# Sch_Raspi_Hat_V2.net
KiCad netlist of a schematic drawn in Altium Designer
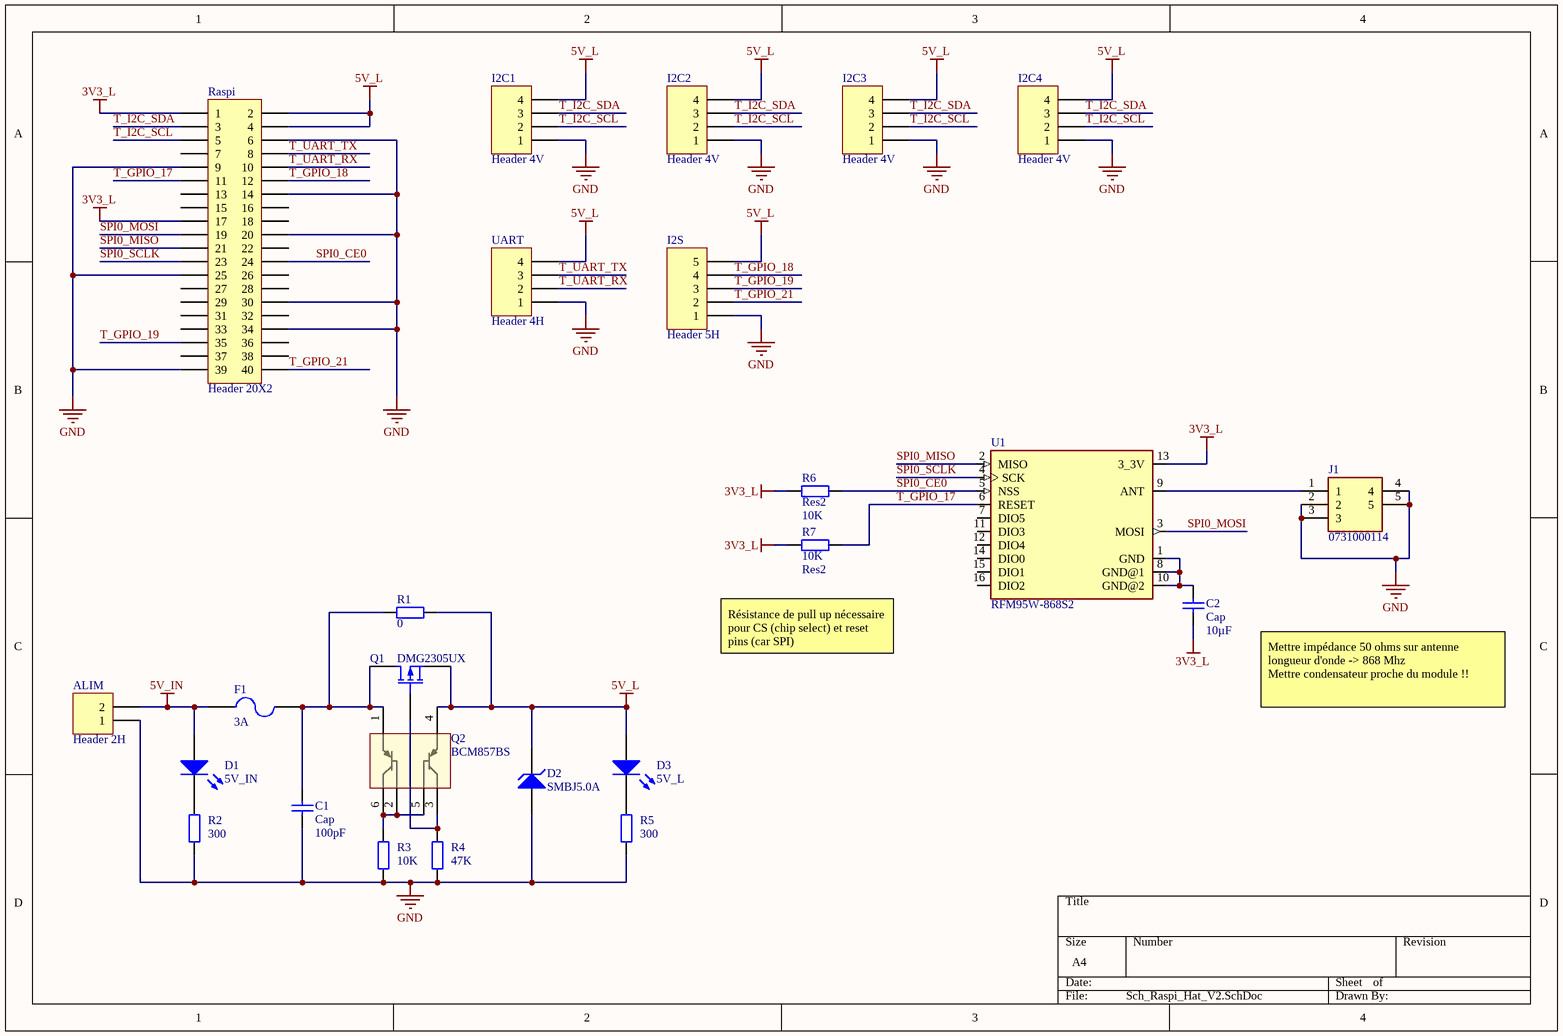
[diagram p0: Sch_Raspi_Hat_V2.SchDoc]

(export (version "E")
  (design (tool "Eeschema 10.0.6"))
  (components
    (comp (ref "ALIM")
      (value "Header 2H")
      (footprint "Molex_MiniFitJr_2x1H")
      (description "Header, 2-Pin, Right Angle")
      (fields (field (name "PUBLISHER") "Altium Limited"))
      (libsource (lib "Miscellaneous Connectors") (part "Header 2H"))
    )
    (comp (ref "C1")
      (value "Cap")
      (footprint "Capacitor 1206")
      (description "Capacitor")
      (fields (field (name "ALTIUM_VALUE") "100pF") (field (name "PUBLISHER") "Altium Limited"))
      (libsource (lib "Miscellaneous Devices") (part "Cap"))
    )
    (comp (ref "C2")
      (value "Cap")
      (footprint "Capacitor 1206")
      (description "Capacitor")
      (fields (field (name "ALTIUM_VALUE") "10µF") (field (name "PUBLISHER") "Altium Limited"))
      (libsource (lib "Miscellaneous Devices") (part "Cap"))
    )
    (comp (ref "D1")
      (value "5V_IN")
      (footprint "KP-3216SEC")
      (description "Typical RED, GREEN, YELLOW, AMBER GaAs LED")
      (fields (field (name "PUBLISHER") "Altium Limited"))
      (libsource (lib "Miscellaneous Devices") (part "LED2"))
    )
    (comp (ref "D2")
      (value "SMBJ5.0A")
      (footprint "SMB")
      (description "Zener Diode")
      (fields (field (name "PUBLISHER") "Altium Limited"))
      (libsource (lib "Miscellaneous Devices") (part "D Zener"))
    )
    (comp (ref "D3")
      (value "5V_L")
      (footprint "KP-3216SEC")
      (description "Typical RED, GREEN, YELLOW, AMBER GaAs LED")
      (fields (field (name "PUBLISHER") "Altium Limited"))
      (libsource (lib "Miscellaneous Devices") (part "LED2"))
    )
    (comp (ref "F1")
      (value "3A")
      (footprint "Resistor 1206")
      (description "Fuse")
      (fields (field (name "PUBLISHER") "Altium Limited"))
      (libsource (lib "Miscellaneous Devices") (part "Fuse 2"))
    )
    (comp (ref "I2C1")
      (value "Header 4V")
      (footprint "B4BXHALFSN")
      (description "Header, 4-Pin, Right Angle")
      (fields (field (name "PUBLISHER") "Altium Limited"))
      (libsource (lib "Miscellaneous Connectors") (part "Header 4H"))
    )
    (comp (ref "I2C2")
      (value "Header 4V")
      (footprint "B4BXHALFSN")
      (description "Header, 4-Pin, Right Angle")
      (fields (field (name "PUBLISHER") "Altium Limited"))
      (libsource (lib "Miscellaneous Connectors") (part "Header 4H"))
    )
    (comp (ref "I2C3")
      (value "Header 4V")
      (footprint "B4BXHALFSN")
      (description "Header, 4-Pin, Right Angle")
      (fields (field (name "PUBLISHER") "Altium Limited"))
      (libsource (lib "Miscellaneous Connectors") (part "Header 4H"))
    )
    (comp (ref "I2C4")
      (value "Header 4V")
      (footprint "B4BXHALFSN")
      (description "Header, 4-Pin, Right Angle")
      (fields (field (name "PUBLISHER") "Altium Limited"))
      (libsource (lib "Miscellaneous Connectors") (part "Header 4H"))
    )
    (comp (ref "I2S")
      (value "Header 5H")
      (footprint "S5B-XH-A")
      (description "Header, 5-Pin, Right Angle")
      (fields (field (name "PUBLISHER") "Altium Limited"))
      (libsource (lib "Miscellaneous Connectors") (part "Header 5H"))
    )
    (comp (ref "J1")
      (value "0731000114")
      (footprint "0731000114")
      (description "Connector")
      (libsource (lib "*") (part "0731000114"))
    )
    (comp (ref "Q1")
      (value "DMG2305UX")
      (footprint "SOT23_L")
      (description "P-Channel MOSFET")
      (fields (field (name "PUBLISHER") "Altium Limited"))
      (libsource (lib "Miscellaneous Devices") (part "MOSFET-P"))
    )
    (comp (ref "Q2")
      (value "BCM857BS")
      (footprint "SOT65P210X110-6N")
      (description "Transistor")
      (libsource (lib "SamacSys") (part "BCM857BS"))
    )
    (comp (ref "R1")
      (value "0")
      (footprint "Resistor 1206")
      (description "Resistor")
      (fields (field (name "Comment") "Res2") (field (name "PUBLISHER") "Altium Limited"))
      (libsource (lib "") (part "Res2_2"))
    )
    (comp (ref "R2")
      (value "300")
      (footprint "Resistor 1206")
      (description "Resistor")
      (fields (field (name "Comment") "Res2") (field (name "PUBLISHER") "Altium Limited"))
      (libsource (lib "Miscellaneous Devices") (part "Res2"))
    )
    (comp (ref "R3")
      (value "10K")
      (footprint "Resistor 1206")
      (description "Resistor")
      (fields (field (name "Comment") "Res2") (field (name "PUBLISHER") "Altium Limited"))
      (libsource (lib "Miscellaneous Devices") (part "Res2"))
    )
    (comp (ref "R4")
      (value "47K")
      (footprint "Resistor 1206")
      (description "Resistor")
      (fields (field (name "Comment") "Res2") (field (name "PUBLISHER") "Altium Limited"))
      (libsource (lib "Miscellaneous Devices") (part "Res2"))
    )
    (comp (ref "R5")
      (value "300")
      (footprint "Resistor 1206")
      (description "Resistor")
      (fields (field (name "Comment") "Res2") (field (name "PUBLISHER") "Altium Limited"))
      (libsource (lib "Miscellaneous Devices") (part "Res2"))
    )
    (comp (ref "R6")
      (value "Res2")
      (footprint "Resistor 1206")
      (description "Resistor")
      (fields (field (name "ALTIUM_VALUE") "10K") (field (name "PUBLISHER") "Altium Limited"))
      (libsource (lib "") (part "Res2_1"))
    )
    (comp (ref "R7")
      (value "Res2")
      (footprint "Resistor 1206")
      (description "Resistor")
      (fields (field (name "ALTIUM_VALUE") "10K") (field (name "PUBLISHER") "Altium Limited"))
      (libsource (lib "") (part "Res2_1"))
    )
    (comp (ref "Raspi")
      (value "Header 20X2")
      (footprint "HDR2X20")
      (description "Header, 20-Pin, Dual row")
      (fields (field (name "PUBLISHER") "Altium Limited"))
      (libsource (lib "Miscellaneous Connectors") (part "Header 20X2"))
    )
    (comp (ref "U1")
      (value "RFM95W-868S2")
      (footprint "XCVR_RFM95W-868S2")
      (description "General ISM < 1GHz LoRaâ„¢ Transceiver Module 868MHz Antenna Not Included Surface Mount")
      (fields (field (name "MF") "RF"))
      (libsource (lib "LORA_RFM95W-868S2") (part "RFM95W-868S2"))
    )
    (comp (ref "UART")
      (value "Header 4H")
      (footprint "S4B-XH-A")
      (description "Header, 4-Pin, Right Angle")
      (fields (field (name "PUBLISHER") "Altium Limited"))
      (libsource (lib "Miscellaneous Connectors") (part "Header 4H"))
    )
  )
  (nets
    (net (code "1") (name "/SPI0_CE0") (class "Default")
      (node (ref "R6") (pin "2") (pinfunction "2_2") (pintype "passive"))
      (node (ref "Raspi") (pin "24") (pinfunction "24_24") (pintype "passive"))
      (node (ref "U1") (pin "5") (pinfunction "NSS_5") (pintype "input"))
    )
    (net (code "2") (name "/SPI0_MISO") (class "Default")
      (node (ref "Raspi") (pin "21") (pinfunction "21_21") (pintype "passive"))
      (node (ref "U1") (pin "2") (pinfunction "MISO_2") (pintype "input"))
    )
    (net (code "3") (name "/SPI0_MOSI") (class "Default")
      (node (ref "Raspi") (pin "19") (pinfunction "19_19") (pintype "passive"))
      (node (ref "U1") (pin "3") (pinfunction "MOSI_3") (pintype "output"))
    )
    (net (code "4") (name "/SPI0_SCLK") (class "Default")
      (node (ref "Raspi") (pin "23") (pinfunction "23_23") (pintype "passive"))
      (node (ref "U1") (pin "4") (pinfunction "SCK_4") (pintype "input"))
    )
    (net (code "5") (name "/T_GPIO_17") (class "Default")
      (node (ref "R7") (pin "2") (pinfunction "2_2") (pintype "passive"))
      (node (ref "Raspi") (pin "11") (pinfunction "11_11") (pintype "passive"))
      (node (ref "U1") (pin "6") (pinfunction "RESET_6") (pintype "bidirectional"))
    )
    (net (code "6") (name "/T_GPIO_18") (class "Default")
      (node (ref "I2S") (pin "4") (pinfunction "4_4") (pintype "passive"))
      (node (ref "Raspi") (pin "12") (pinfunction "12_12") (pintype "passive"))
    )
    (net (code "7") (name "/T_GPIO_19") (class "Default")
      (node (ref "I2S") (pin "3") (pinfunction "3_3") (pintype "passive"))
      (node (ref "Raspi") (pin "35") (pinfunction "35_35") (pintype "passive"))
    )
    (net (code "8") (name "/T_GPIO_21") (class "Default")
      (node (ref "I2S") (pin "2") (pinfunction "2_2") (pintype "passive"))
      (node (ref "Raspi") (pin "40") (pinfunction "40_40") (pintype "passive"))
    )
    (net (code "9") (name "/T_I2C_SCL") (class "Default")
      (node (ref "I2C1") (pin "2") (pinfunction "2_2") (pintype "passive"))
      (node (ref "I2C2") (pin "2") (pinfunction "2_2") (pintype "passive"))
      (node (ref "I2C3") (pin "2") (pinfunction "2_2") (pintype "passive"))
      (node (ref "I2C4") (pin "2") (pinfunction "2_2") (pintype "passive"))
      (node (ref "Raspi") (pin "5") (pinfunction "5_5") (pintype "passive"))
    )
    (net (code "10") (name "/T_I2C_SDA") (class "Default")
      (node (ref "I2C1") (pin "3") (pinfunction "3_3") (pintype "passive"))
      (node (ref "I2C2") (pin "3") (pinfunction "3_3") (pintype "passive"))
      (node (ref "I2C3") (pin "3") (pinfunction "3_3") (pintype "passive"))
      (node (ref "I2C4") (pin "3") (pinfunction "3_3") (pintype "passive"))
      (node (ref "Raspi") (pin "3") (pinfunction "3_3") (pintype "passive"))
    )
    (net (code "11") (name "/T_UART_RX") (class "Default")
      (node (ref "Raspi") (pin "10") (pinfunction "10_10") (pintype "passive"))
      (node (ref "UART") (pin "2") (pinfunction "2_2") (pintype "passive"))
    )
    (net (code "12") (name "/T_UART_TX") (class "Default")
      (node (ref "Raspi") (pin "8") (pinfunction "8_8") (pintype "passive"))
      (node (ref "UART") (pin "3") (pinfunction "3_3") (pintype "passive"))
    )
    (net (code "13") (name "3V3_L") (class "Default")
      (node (ref "C2") (pin "1") (pinfunction "1_1") (pintype "passive"))
      (node (ref "R6") (pin "1") (pinfunction "1_1") (pintype "passive"))
      (node (ref "R7") (pin "1") (pinfunction "1_1") (pintype "passive"))
      (node (ref "Raspi") (pin "1") (pinfunction "1_1") (pintype "passive"))
      (node (ref "Raspi") (pin "17") (pinfunction "17_17") (pintype "passive"))
      (node (ref "U1") (pin "13") (pinfunction "3_3V_13") (pintype "power_in"))
    )
    (net (code "14") (name "5V_IN") (class "Default")
      (node (ref "ALIM") (pin "2") (pinfunction "2_2") (pintype "passive"))
      (node (ref "D1") (pin "1") (pinfunction "A_1") (pintype "passive"))
      (node (ref "F1") (pin "1") (pinfunction "1_1") (pintype "passive"))
    )
    (net (code "15") (name "5V_L") (class "Default")
      (node (ref "D2") (pin "2") (pinfunction "K_2") (pintype "passive"))
      (node (ref "D3") (pin "1") (pinfunction "A_1") (pintype "passive"))
      (node (ref "I2C1") (pin "4") (pinfunction "4_4") (pintype "passive"))
      (node (ref "I2C2") (pin "4") (pinfunction "4_4") (pintype "passive"))
      (node (ref "I2C3") (pin "4") (pinfunction "4_4") (pintype "passive"))
      (node (ref "I2C4") (pin "4") (pinfunction "4_4") (pintype "passive"))
      (node (ref "I2S") (pin "5") (pinfunction "5_5") (pintype "passive"))
      (node (ref "Q1") (pin "3") (pinfunction "S_3") (pintype "passive"))
      (node (ref "Q2") (pin "4") (pinfunction "EMITTER_TR2_4") (pintype "passive"))
      (node (ref "R1") (pin "1") (pinfunction "1_1") (pintype "passive"))
      (node (ref "Raspi") (pin "2") (pinfunction "2_2") (pintype "passive"))
      (node (ref "Raspi") (pin "4") (pinfunction "4_4") (pintype "passive"))
      (node (ref "UART") (pin "4") (pinfunction "4_4") (pintype "passive"))
    )
    (net (code "16") (name "GND") (class "Default")
      (node (ref "ALIM") (pin "1") (pinfunction "1_1") (pintype "passive"))
      (node (ref "C1") (pin "1") (pinfunction "1_1") (pintype "passive"))
      (node (ref "D2") (pin "1") (pinfunction "A_1") (pintype "passive"))
      (node (ref "I2C1") (pin "1") (pinfunction "1_1") (pintype "passive"))
      (node (ref "I2C2") (pin "1") (pinfunction "1_1") (pintype "passive"))
      (node (ref "I2C3") (pin "1") (pinfunction "1_1") (pintype "passive"))
      (node (ref "I2C4") (pin "1") (pinfunction "1_1") (pintype "passive"))
      (node (ref "I2S") (pin "1") (pinfunction "1_1") (pintype "passive"))
      (node (ref "J1") (pin "2") (pinfunction "2_2") (pintype "passive"))
      (node (ref "J1") (pin "3") (pinfunction "3_3") (pintype "passive"))
      (node (ref "J1") (pin "4") (pinfunction "4_4") (pintype "passive"))
      (node (ref "J1") (pin "5") (pinfunction "5_5") (pintype "passive"))
      (node (ref "R2") (pin "1") (pinfunction "1_1") (pintype "passive"))
      (node (ref "R3") (pin "1") (pinfunction "1_1") (pintype "passive"))
      (node (ref "R4") (pin "1") (pinfunction "1_1") (pintype "passive"))
      (node (ref "R5") (pin "1") (pinfunction "1_1") (pintype "passive"))
      (node (ref "Raspi") (pin "14") (pinfunction "14_14") (pintype "passive"))
      (node (ref "Raspi") (pin "20") (pinfunction "20_20") (pintype "passive"))
      (node (ref "Raspi") (pin "25") (pinfunction "25_25") (pintype "passive"))
      (node (ref "Raspi") (pin "30") (pinfunction "30_30") (pintype "passive"))
      (node (ref "Raspi") (pin "34") (pinfunction "34_34") (pintype "passive"))
      (node (ref "Raspi") (pin "39") (pinfunction "39_39") (pintype "passive"))
      (node (ref "Raspi") (pin "6") (pinfunction "6_6") (pintype "passive"))
      (node (ref "Raspi") (pin "9") (pinfunction "9_9") (pintype "passive"))
      (node (ref "UART") (pin "1") (pinfunction "1_1") (pintype "passive"))
    )
    (net (code "17") (name "Net-(D1-K)") (class "Default")
      (node (ref "D1") (pin "2") (pinfunction "K_2") (pintype "passive"))
      (node (ref "R2") (pin "2") (pinfunction "2_2") (pintype "passive"))
    )
    (net (code "18") (name "Net-(D3-K)") (class "Default")
      (node (ref "D3") (pin "2") (pinfunction "K_2") (pintype "passive"))
      (node (ref "R5") (pin "2") (pinfunction "2_2") (pintype "passive"))
    )
    (net (code "19") (name "Net-(Q1-D)") (class "Default")
      (node (ref "C1") (pin "2") (pinfunction "2_2") (pintype "passive"))
      (node (ref "F1") (pin "2") (pinfunction "2_2") (pintype "passive"))
      (node (ref "Q1") (pin "1") (pinfunction "D_1") (pintype "passive"))
      (node (ref "Q2") (pin "1") (pinfunction "EMITTER_TR1_1") (pintype "passive"))
      (node (ref "R1") (pin "2") (pinfunction "2_2") (pintype "passive"))
    )
    (net (code "20") (name "Net-(Q1-G)") (class "Default")
      (node (ref "Q1") (pin "2") (pinfunction "G_2") (pintype "passive"))
      (node (ref "Q2") (pin "3") (pinfunction "COLLECTOR_TR2_3") (pintype "passive"))
      (node (ref "R4") (pin "2") (pinfunction "2_2") (pintype "passive"))
    )
    (net (code "21") (name "Net-(Q2-BASE_TR1)") (class "Default")
      (node (ref "Q2") (pin "2") (pinfunction "BASE_TR1_2") (pintype "passive"))
      (node (ref "Q2") (pin "5") (pinfunction "BASE_TR2_5") (pintype "passive"))
      (node (ref "Q2") (pin "6") (pinfunction "COLLECTOR_TR1_6") (pintype "passive"))
      (node (ref "R3") (pin "2") (pinfunction "2_2") (pintype "passive"))
    )
    (net (code "22") (name "Net-(U1-ANT)") (class "Default")
      (node (ref "J1") (pin "1") (pinfunction "1_1") (pintype "passive"))
      (node (ref "U1") (pin "9") (pinfunction "ANT_9") (pintype "passive"))
    )
    (net (code "23") (name "Net-(U1-GND)") (class "Default")
      (node (ref "C2") (pin "2") (pinfunction "2_2") (pintype "passive"))
      (node (ref "U1") (pin "1") (pinfunction "GND_1") (pintype "power_in"))
      (node (ref "U1") (pin "10") (pinfunction "GND@2_10") (pintype "power_in"))
      (node (ref "U1") (pin "8") (pinfunction "GND@1_8") (pintype "power_in"))
    )
    (net (code "24") (name "unconnected-(Raspi-Pad7)") (class "Default")
      (node (ref "Raspi") (pin "7") (pinfunction "7_7") (pintype "passive"))
    )
    (net (code "25") (name "unconnected-(Raspi-Pad13)") (class "Default")
      (node (ref "Raspi") (pin "13") (pinfunction "13_13") (pintype "passive"))
    )
    (net (code "26") (name "unconnected-(Raspi-Pad15)") (class "Default")
      (node (ref "Raspi") (pin "15") (pinfunction "15_15") (pintype "passive"))
    )
    (net (code "27") (name "unconnected-(Raspi-Pad16)") (class "Default")
      (node (ref "Raspi") (pin "16") (pinfunction "16_16") (pintype "passive"))
    )
    (net (code "28") (name "unconnected-(Raspi-Pad18)") (class "Default")
      (node (ref "Raspi") (pin "18") (pinfunction "18_18") (pintype "passive"))
    )
    (net (code "29") (name "unconnected-(Raspi-Pad22)") (class "Default")
      (node (ref "Raspi") (pin "22") (pinfunction "22_22") (pintype "passive"))
    )
    (net (code "30") (name "unconnected-(Raspi-Pad26)") (class "Default")
      (node (ref "Raspi") (pin "26") (pinfunction "26_26") (pintype "passive"))
    )
    (net (code "31") (name "unconnected-(Raspi-Pad27)") (class "Default")
      (node (ref "Raspi") (pin "27") (pinfunction "27_27") (pintype "passive"))
    )
    (net (code "32") (name "unconnected-(Raspi-Pad28)") (class "Default")
      (node (ref "Raspi") (pin "28") (pinfunction "28_28") (pintype "passive"))
    )
    (net (code "33") (name "unconnected-(Raspi-Pad29)") (class "Default")
      (node (ref "Raspi") (pin "29") (pinfunction "29_29") (pintype "passive"))
    )
    (net (code "34") (name "unconnected-(Raspi-Pad31)") (class "Default")
      (node (ref "Raspi") (pin "31") (pinfunction "31_31") (pintype "passive"))
    )
    (net (code "35") (name "unconnected-(Raspi-Pad32)") (class "Default")
      (node (ref "Raspi") (pin "32") (pinfunction "32_32") (pintype "passive"))
    )
    (net (code "36") (name "unconnected-(Raspi-Pad33)") (class "Default")
      (node (ref "Raspi") (pin "33") (pinfunction "33_33") (pintype "passive"))
    )
    (net (code "37") (name "unconnected-(Raspi-Pad36)") (class "Default")
      (node (ref "Raspi") (pin "36") (pinfunction "36_36") (pintype "passive"))
    )
    (net (code "38") (name "unconnected-(Raspi-Pad37)") (class "Default")
      (node (ref "Raspi") (pin "37") (pinfunction "37_37") (pintype "passive"))
    )
    (net (code "39") (name "unconnected-(Raspi-Pad38)") (class "Default")
      (node (ref "Raspi") (pin "38") (pinfunction "38_38") (pintype "passive"))
    )
    (net (code "40") (name "unconnected-(U1-DIO0-Pad14)") (class "Default")
      (node (ref "U1") (pin "14") (pinfunction "DIO0_14") (pintype "bidirectional"))
    )
    (net (code "41") (name "unconnected-(U1-DIO1-Pad15)") (class "Default")
      (node (ref "U1") (pin "15") (pinfunction "DIO1_15") (pintype "bidirectional"))
    )
    (net (code "42") (name "unconnected-(U1-DIO2-Pad16)") (class "Default")
      (node (ref "U1") (pin "16") (pinfunction "DIO2_16") (pintype "bidirectional"))
    )
    (net (code "43") (name "unconnected-(U1-DIO3-Pad11)") (class "Default")
      (node (ref "U1") (pin "11") (pinfunction "DIO3_11") (pintype "bidirectional"))
    )
    (net (code "44") (name "unconnected-(U1-DIO4-Pad12)") (class "Default")
      (node (ref "U1") (pin "12") (pinfunction "DIO4_12") (pintype "bidirectional"))
    )
    (net (code "45") (name "unconnected-(U1-DIO5-Pad7)") (class "Default")
      (node (ref "U1") (pin "7") (pinfunction "DIO5_7") (pintype "bidirectional"))
    )
  )
)
